# PowerSupply.net
KiCad netlist of a schematic drawn in Altium Designer
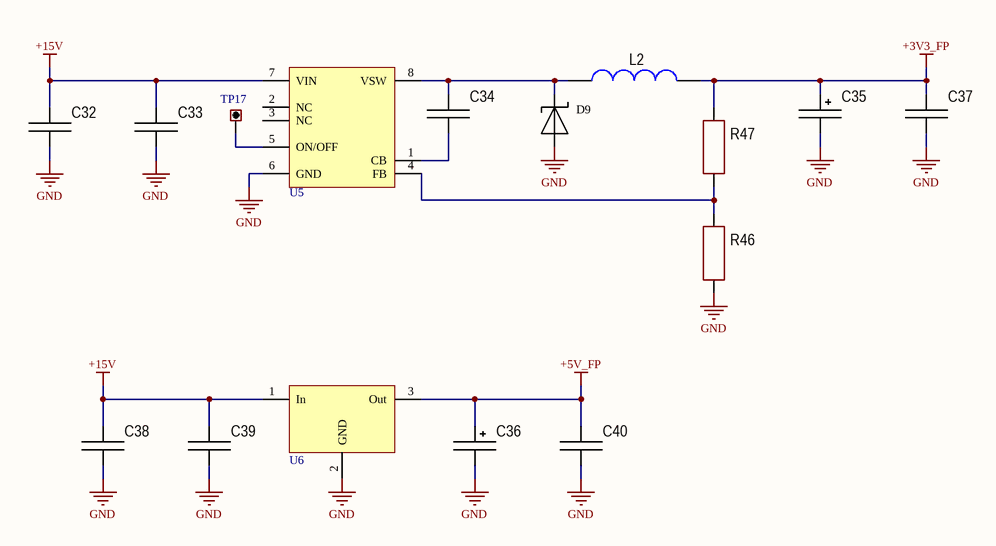
[diagram p0: PowerSupply.SchDoc]

(export (version "E")
  (design (tool "Eeschema 10.0.6"))
  (components
    (comp (ref "C32")
      (value "~")
      (footprint "StandardCase:CAP: 1210")
      (fields
        (field (name "MANUFACTURER") "Yageo")
        (field (name "PARTNUMBER") "CC1206KRX7R9BB104")
        (field (name "VALUEMANUFACTURERPARTNUMBER") "Ceramic capacitor, 22μF, 1206")
      )
      (libsource (lib "Capacitor") (part "Ceramic_1206"))
    )
    (comp (ref "C33")
      (value "~")
      (footprint "StandardCase:CAP: 1206")
      (fields
        (field (name "MANUFACTURER") "Yageo")
        (field (name "PARTNUMBER") "CC1206KRX7R9BB104")
        (field (name "VALUEMANUFACTURERPARTNUMBER") "Ceramic capacitor, 0.1μF, 1206")
      )
      (libsource (lib "Capacitor") (part "Ceramic_1206"))
    )
    (comp (ref "C34")
      (value "~")
      (footprint "StandardCase:CAP: 1206")
      (fields
        (field (name "MANUFACTURER") "Yageo")
        (field (name "PARTNUMBER") "CC1206KRX7R9BB104")
        (field (name "VALUEMANUFACTURERPARTNUMBER") "Ceramic capacitor, 10nF, 1206")
      )
      (libsource (lib "Capacitor") (part "Ceramic_1206"))
    )
    (comp (ref "C35")
      (value "~")
      (footprint "FP_lib_PCB:CAPAE7866X58L")
      (fields
        (field (name "MANUFACTURER") "Wurth")
        (field (name "PARTNUMBER") "EEEFK1E470P")
        (field (name "VALUEMANUFACTURERPARTNUMBER") "Aluminium capacitor, EEEFK1E470P, 47μF, 25V, D")
      )
      (libsource (lib "Capacitor") (part "Aluminium"))
    )
    (comp (ref "C36")
      (value "~")
      (footprint "FP_lib_PCB:CAPAE7866X58L")
      (fields
        (field (name "MANUFACTURER") "Wurth")
        (field (name "PARTNUMBER") "EEEFK1E470P")
        (field (name "VALUEMANUFACTURERPARTNUMBER") "Aluminium capacitor, EEEFK1E470P, 47μF, 25V, D")
      )
      (libsource (lib "Capacitor") (part "Aluminium"))
    )
    (comp (ref "C37")
      (value "~")
      (footprint "StandardCase:CAP: 1206")
      (fields
        (field (name "MANUFACTURER") "Yageo")
        (field (name "PARTNUMBER") "CC1206KRX7R9BB104")
        (field (name "VALUEMANUFACTURERPARTNUMBER") "Ceramic capacitor, 0.1μF, 1206")
      )
      (libsource (lib "Capacitor") (part "Ceramic_1206"))
    )
    (comp (ref "C38")
      (value "~")
      (footprint "StandardCase:CAP: 1210")
      (fields
        (field (name "MANUFACTURER") "Yageo")
        (field (name "PARTNUMBER") "CC1206KRX7R9BB104")
        (field (name "VALUEMANUFACTURERPARTNUMBER") "Ceramic capacitor, 22μF, 1206")
      )
      (libsource (lib "Capacitor") (part "Ceramic_1206"))
    )
    (comp (ref "C39")
      (value "~")
      (footprint "StandardCase:CAP: 1206")
      (fields
        (field (name "MANUFACTURER") "Yageo")
        (field (name "PARTNUMBER") "CC1206KRX7R9BB104")
        (field (name "VALUEMANUFACTURERPARTNUMBER") "Ceramic capacitor, 10nF, 1206")
      )
      (libsource (lib "Capacitor") (part "Ceramic_1206"))
    )
    (comp (ref "C40")
      (value "~")
      (footprint "StandardCase:CAP: 1206")
      (fields
        (field (name "MANUFACTURER") "Yageo")
        (field (name "PARTNUMBER") "CC1206KRX7R9BB104")
        (field (name "VALUEMANUFACTURERPARTNUMBER") "Ceramic capacitor, 0.1μF, 1206")
      )
      (libsource (lib "Capacitor") (part "Ceramic_1206"))
    )
    (comp (ref "D9")
      (value "~")
      (footprint "StandardCase:DIODE: SMB")
      (fields
        (field (name "VALUEMANUFACTURERPARTNUMBER") "MBRS260T3G, SMB")
        (field (name "PARTNUMBER") "MBRS260T3G")
      )
      (libsource (lib "FP_lib_SCH") (part "MBRS260T3G"))
    )
    (comp (ref "L2")
      (value "~")
      (footprint "FP_lib_PCB:7447720181@WURTH")
      (fields
        (field (name "MANUFACTURER") "WURTH")
        (field (name "PARTNUMBER") "7447720181")
        (field (name "VALUEMANUFACTURERPARTNUMBER") "Fixed inductor, WURTH, 7447720181, 180μH")
      )
      (libsource (lib "Inductor") (part "Inductor_0805"))
    )
    (comp (ref "R46")
      (value "~")
      (footprint "StandardCase:RES: 1206")
      (fields
        (field (name "MANUFACTURER") "Yageo")
        (field (name "PARTNUMBER") "RC1206JR-07100RL")
        (field (name "VALUEMANUFACTURERPARTNUMBER") "Resistor, 1K, 1206")
      )
      (libsource (lib "Resistor") (part "Resistor_1206"))
    )
    (comp (ref "R47")
      (value "~")
      (footprint "StandardCase:RES: 1206")
      (fields
        (field (name "MANUFACTURER") "Yageo")
        (field (name "PARTNUMBER") "RC1206JR-07100RL")
        (field (name "VALUEMANUFACTURERPARTNUMBER") "Resistor, 1.74K, 1206")
      )
      (libsource (lib "Resistor") (part "Resistor_1206"))
    )
    (comp (ref "TP17")
      (value "Test_Point")
      (footprint "FP_lib_PCB:Test_Point")
      (libsource (lib "FP_lib_SCH") (part "Test_Point"))
    )
    (comp (ref "U5")
      (value "~")
      (footprint "StandardCase:8-SOIC")
      (fields
        (field (name "VALUEMANUFACTURERPARTNUMBER") "LM2675, SOIC-8")
        (field (name "PARTNUMBER") "LM2675")
      )
      (libsource (lib "FP_lib_SCH") (part "LM2675"))
    )
    (comp (ref "U6")
      (value "~")
      (footprint "StandardCase:DPAK")
      (fields
        (field (name "VALUEMANUFACTURERPARTNUMBER") "LM78M05CDT, DPAK")
        (field (name "PARTNUMBER") "LM78M05CDT")
      )
      (libsource (lib "FP_lib_SCH") (part "LM78M05CDT"))
    )
  )
  (nets
    (net (code "1") (name "+3V3_FP") (class "Default")
      (node (ref "C35") (pin "1") (pinfunction "1_1") (pintype "power_in"))
      (node (ref "C37") (pin "2") (pinfunction "2_2") (pintype "power_in"))
      (node (ref "L2") (pin "1") (pinfunction "1_1") (pintype "passive"))
      (node (ref "R47") (pin "2") (pinfunction "2_2") (pintype "passive"))
    )
    (net (code "2") (name "+5V_FP") (class "Default")
      (node (ref "C36") (pin "1") (pinfunction "1_1") (pintype "power_in"))
      (node (ref "C40") (pin "2") (pinfunction "2_2") (pintype "power_in"))
      (node (ref "U6") (pin "3") (pinfunction "Out_3") (pintype "passive"))
    )
    (net (code "3") (name "+15V") (class "Default")
      (node (ref "C32") (pin "2") (pinfunction "2_2") (pintype "power_in"))
      (node (ref "C33") (pin "2") (pinfunction "2_2") (pintype "power_in"))
      (node (ref "C38") (pin "2") (pinfunction "2_2") (pintype "power_in"))
      (node (ref "C39") (pin "2") (pinfunction "2_2") (pintype "power_in"))
      (node (ref "U5") (pin "7") (pinfunction "VIN_7") (pintype "passive"))
      (node (ref "U6") (pin "1") (pinfunction "In_1") (pintype "passive"))
    )
    (net (code "4") (name "GND") (class "Default")
      (node (ref "C32") (pin "1") (pinfunction "1_1") (pintype "power_in"))
      (node (ref "C33") (pin "1") (pinfunction "1_1") (pintype "power_in"))
      (node (ref "C35") (pin "2") (pinfunction "2_2") (pintype "power_in"))
      (node (ref "C36") (pin "2") (pinfunction "2_2") (pintype "power_in"))
      (node (ref "C37") (pin "1") (pinfunction "1_1") (pintype "power_in"))
      (node (ref "C38") (pin "1") (pinfunction "1_1") (pintype "power_in"))
      (node (ref "C39") (pin "1") (pinfunction "1_1") (pintype "power_in"))
      (node (ref "C40") (pin "1") (pinfunction "1_1") (pintype "power_in"))
      (node (ref "D9") (pin "1") (pinfunction "1_1") (pintype "passive"))
      (node (ref "R46") (pin "1") (pinfunction "1_1") (pintype "passive"))
      (node (ref "U5") (pin "6") (pinfunction "GND_6") (pintype "passive"))
      (node (ref "U6") (pin "2") (pinfunction "GND_2") (pintype "passive"))
    )
    (net (code "5") (name "Net-(U5-CB)") (class "Default")
      (node (ref "C34") (pin "1") (pinfunction "1_1") (pintype "power_in"))
      (node (ref "U5") (pin "1") (pinfunction "CB_1") (pintype "passive"))
    )
    (net (code "6") (name "Net-(U5-FB)") (class "Default")
      (node (ref "R46") (pin "2") (pinfunction "2_2") (pintype "passive"))
      (node (ref "R47") (pin "1") (pinfunction "1_1") (pintype "passive"))
      (node (ref "U5") (pin "4") (pinfunction "FB_4") (pintype "passive"))
    )
    (net (code "7") (name "Net-(U5-ON{slash}OFF)") (class "Default")
      (node (ref "TP17") (pin "1") (pinfunction "1_1") (pintype "passive"))
      (node (ref "U5") (pin "5") (pinfunction "ON/OFF_5") (pintype "passive"))
    )
    (net (code "8") (name "Net-(U5-VSW)") (class "Default")
      (node (ref "C34") (pin "2") (pinfunction "2_2") (pintype "power_in"))
      (node (ref "D9") (pin "2") (pinfunction "2_2") (pintype "passive"))
      (node (ref "L2") (pin "2") (pinfunction "2_2") (pintype "passive"))
      (node (ref "U5") (pin "8") (pinfunction "VSW_8") (pintype "passive"))
    )
    (net (code "9") (name "unconnected-(U5-NC-Pad2)") (class "Default")
      (node (ref "U5") (pin "2") (pinfunction "NC_2") (pintype "passive"))
    )
    (net (code "10") (name "unconnected-(U5-NC-Pad3)") (class "Default")
      (node (ref "U5") (pin "3") (pinfunction "NC_3") (pintype "passive"))
    )
  )
)
